# MD029A_HalfBridges.net
KiCad netlist of a schematic drawn in Altium Designer
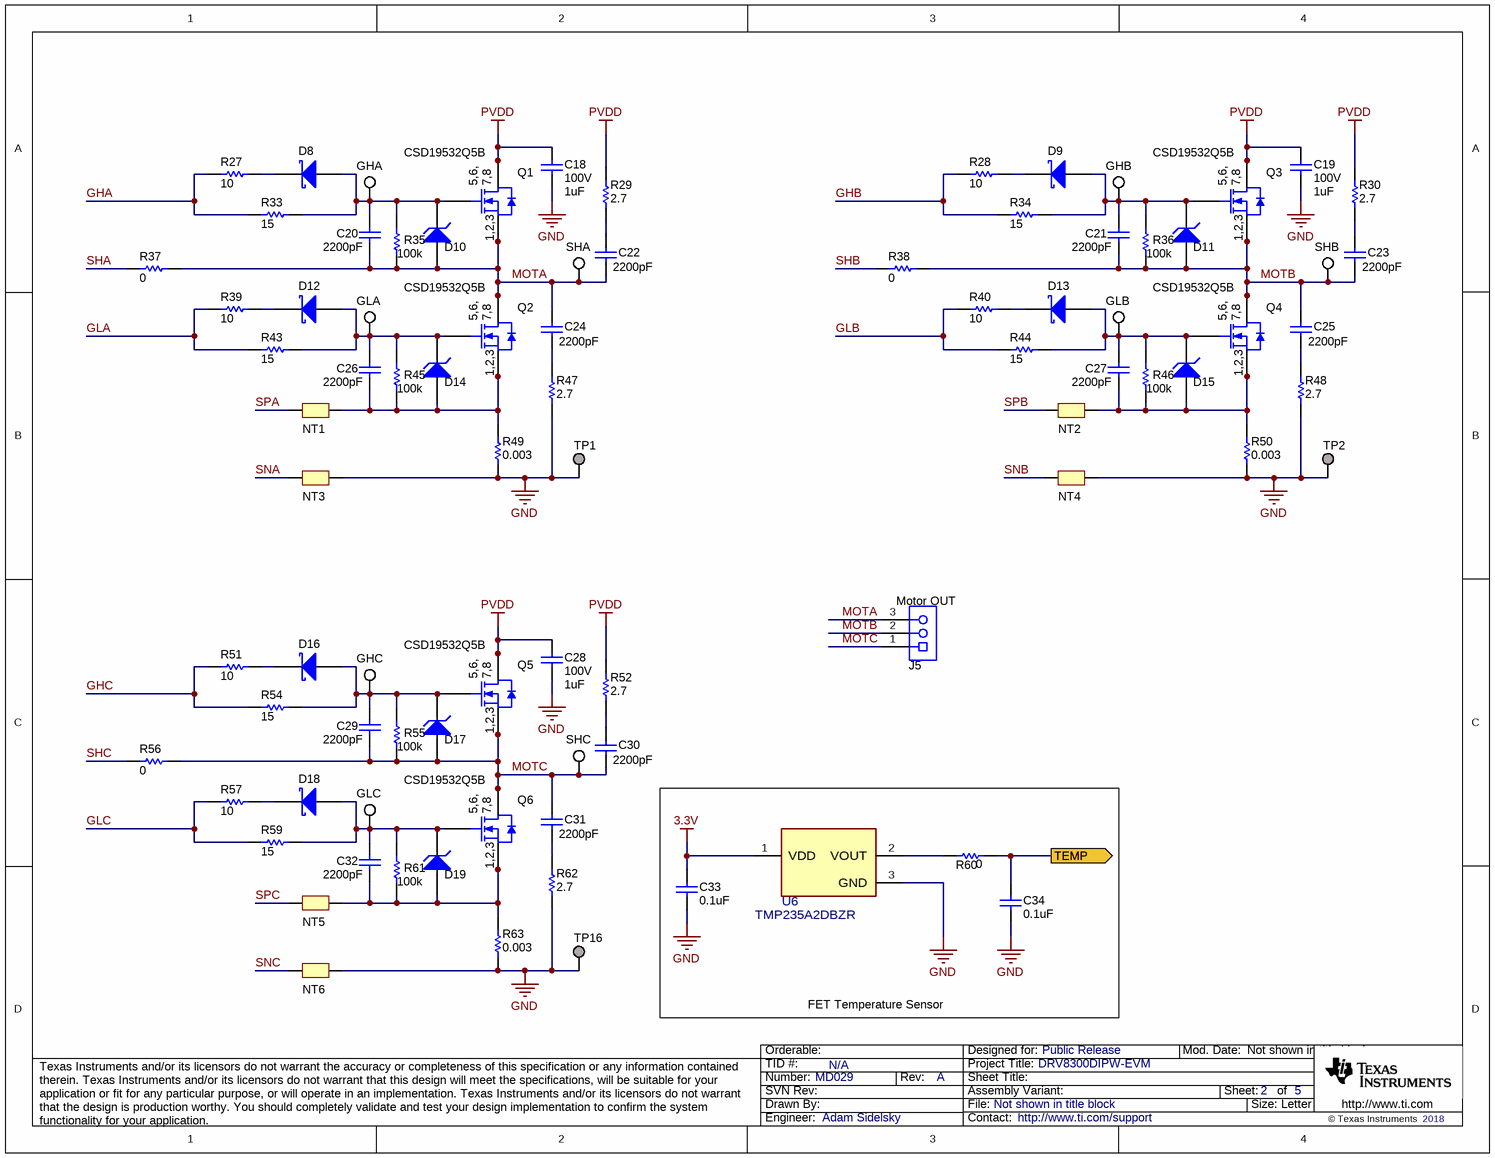
[diagram p0: MD029A_HalfBridges.SchDoc]

(export (version "E")
  (design (tool "Eeschema 10.0.6"))
  (components
    (comp (ref "C18")
      (value "CGA6M2X7R2A105K200AA")
      (footprint "1210_220L")
      (description "CAP, CERM, 1 uF, 100 V, +/- 10%, X7R, AEC-Q200 Grade 1, 1210")
      (fields
        (field (name "MANUFACTURER") "TDK")
        (field (name "VDC_V") "100V")
        (field (name "VALUEDISPLAYED") "1uF")
        (field (name "PUBLISHER") "Texas Instruments")
      )
      (libsource (lib "Altium Vault - TI") (part "Capacitor"))
    )
    (comp (ref "C19")
      (value "CGA6M2X7R2A105K200AA")
      (footprint "1210_220L")
      (description "CAP, CERM, 1 uF, 100 V, +/- 10%, X7R, AEC-Q200 Grade 1, 1210")
      (fields
        (field (name "MANUFACTURER") "TDK")
        (field (name "VDC_V") "100V")
        (field (name "VALUEDISPLAYED") "1uF")
        (field (name "PUBLISHER") "Texas Instruments")
      )
      (libsource (lib "Altium Vault - TI") (part "Capacitor"))
    )
    (comp (ref "C20")
      (value "06031C222KAT2A")
      (footprint "0603L")
      (description "CAP, CERM, 2200 pF, 100 V, +/- 10%, X7R, 0603")
      (fields
        (field (name "MANUFACTURER") "AVX")
        (field (name "VALUEDISPLAYED") "2200pF")
        (field (name "PUBLISHER") "Texas Instruments")
      )
      (libsource (lib "Altium Vault - TI") (part "CMP-0006737-4"))
    )
    (comp (ref "C21")
      (value "06031C222KAT2A")
      (footprint "0603L")
      (description "CAP, CERM, 2200 pF, 100 V, +/- 10%, X7R, 0603")
      (fields
        (field (name "MANUFACTURER") "AVX")
        (field (name "VALUEDISPLAYED") "2200pF")
        (field (name "PUBLISHER") "Texas Instruments")
      )
      (libsource (lib "Altium Vault - TI") (part "CMP-0006737-4"))
    )
    (comp (ref "C22")
      (value "GRM188R72A222KA01D")
      (footprint "0603L")
      (description "CAP, CERM, 2200 pF, 100 V, +/- 10%, X7R, 0603")
      (fields
        (field (name "MANUFACTURER") "MuRata")
        (field (name "VALUEDISPLAYED") "2200pF")
        (field (name "PUBLISHER") "Texas Instruments")
      )
      (libsource (lib "Altium Vault - TI") (part "CMP-0007475-4"))
    )
    (comp (ref "C23")
      (value "GRM188R72A222KA01D")
      (footprint "0603L")
      (description "CAP, CERM, 2200 pF, 100 V, +/- 10%, X7R, 0603")
      (fields
        (field (name "MANUFACTURER") "MuRata")
        (field (name "VALUEDISPLAYED") "2200pF")
        (field (name "PUBLISHER") "Texas Instruments")
      )
      (libsource (lib "Altium Vault - TI") (part "CMP-0007475-4"))
    )
    (comp (ref "C24")
      (value "GRM188R72A222KA01D")
      (footprint "0603L")
      (description "CAP, CERM, 2200 pF, 100 V, +/- 10%, X7R, 0603")
      (fields
        (field (name "MANUFACTURER") "MuRata")
        (field (name "VALUEDISPLAYED") "2200pF")
        (field (name "PUBLISHER") "Texas Instruments")
      )
      (libsource (lib "Altium Vault - TI") (part "CMP-0007475-4"))
    )
    (comp (ref "C25")
      (value "GRM188R72A222KA01D")
      (footprint "0603L")
      (description "CAP, CERM, 2200 pF, 100 V, +/- 10%, X7R, 0603")
      (fields
        (field (name "MANUFACTURER") "MuRata")
        (field (name "VALUEDISPLAYED") "2200pF")
        (field (name "PUBLISHER") "Texas Instruments")
      )
      (libsource (lib "Altium Vault - TI") (part "CMP-0007475-4"))
    )
    (comp (ref "C26")
      (value "06031C222KAT2A")
      (footprint "0603L")
      (description "CAP, CERM, 2200 pF, 100 V, +/- 10%, X7R, 0603")
      (fields
        (field (name "MANUFACTURER") "AVX")
        (field (name "VALUEDISPLAYED") "2200pF")
        (field (name "PUBLISHER") "Texas Instruments")
      )
      (libsource (lib "Altium Vault - TI") (part "CMP-0006737-4"))
    )
    (comp (ref "C27")
      (value "06031C222KAT2A")
      (footprint "0603L")
      (description "CAP, CERM, 2200 pF, 100 V, +/- 10%, X7R, 0603")
      (fields
        (field (name "MANUFACTURER") "AVX")
        (field (name "VALUEDISPLAYED") "2200pF")
        (field (name "PUBLISHER") "Texas Instruments")
      )
      (libsource (lib "Altium Vault - TI") (part "CMP-0006737-4"))
    )
    (comp (ref "C28")
      (value "CGA6M2X7R2A105K200AA")
      (footprint "1210_220L")
      (description "CAP, CERM, 1 uF, 100 V, +/- 10%, X7R, AEC-Q200 Grade 1, 1210")
      (fields
        (field (name "MANUFACTURER") "TDK")
        (field (name "VDC_V") "100V")
        (field (name "VALUEDISPLAYED") "1uF")
        (field (name "PUBLISHER") "Texas Instruments")
      )
      (libsource (lib "Altium Vault - TI") (part "Capacitor"))
    )
    (comp (ref "C29")
      (value "06031C222KAT2A")
      (footprint "0603L")
      (description "CAP, CERM, 2200 pF, 100 V, +/- 10%, X7R, 0603")
      (fields
        (field (name "MANUFACTURER") "AVX")
        (field (name "VALUEDISPLAYED") "2200pF")
        (field (name "PUBLISHER") "Texas Instruments")
      )
      (libsource (lib "Altium Vault - TI") (part "CMP-0006737-4"))
    )
    (comp (ref "C30")
      (value "GRM188R72A222KA01D")
      (footprint "0603L")
      (description "CAP, CERM, 2200 pF, 100 V, +/- 10%, X7R, 0603")
      (fields
        (field (name "MANUFACTURER") "MuRata")
        (field (name "VALUEDISPLAYED") "2200pF")
        (field (name "PUBLISHER") "Texas Instruments")
      )
      (libsource (lib "Altium Vault - TI") (part "CMP-0007475-4"))
    )
    (comp (ref "C31")
      (value "GRM188R72A222KA01D")
      (footprint "0603L")
      (description "CAP, CERM, 2200 pF, 100 V, +/- 10%, X7R, 0603")
      (fields
        (field (name "MANUFACTURER") "MuRata")
        (field (name "VALUEDISPLAYED") "2200pF")
        (field (name "PUBLISHER") "Texas Instruments")
      )
      (libsource (lib "Altium Vault - TI") (part "CMP-0007475-4"))
    )
    (comp (ref "C32")
      (value "06031C222KAT2A")
      (footprint "0603L")
      (description "CAP, CERM, 2200 pF, 100 V, +/- 10%, X7R, 0603")
      (fields
        (field (name "MANUFACTURER") "AVX")
        (field (name "VALUEDISPLAYED") "2200pF")
        (field (name "PUBLISHER") "Texas Instruments")
      )
      (libsource (lib "Altium Vault - TI") (part "CMP-0006737-4"))
    )
    (comp (ref "C33")
      (value "C0603C104J4RACTU")
      (footprint "0603L")
      (description "CAP, CERM, 0.1 uF, 16 V, +/- 5%, X7R, 0603")
      (fields
        (field (name "VALUEDISPLAYED") "0.1uF")
        (field (name "MANUFACTURER") "Kemet")
        (field (name "PUBLISHER") "Texas Instruments")
      )
      (libsource (lib "Altium Vault - TI") (part "CMP-0006857-4"))
    )
    (comp (ref "C34")
      (value "C0603C104J4RACTU")
      (footprint "0603L")
      (description "CAP, CERM, 0.1 uF, 16 V, +/- 5%, X7R, 0603")
      (fields
        (field (name "VALUEDISPLAYED") "0.1uF")
        (field (name "MANUFACTURER") "Kemet")
        (field (name "PUBLISHER") "Texas Instruments")
      )
      (libsource (lib "Altium Vault - TI") (part "CMP-0006857-4"))
    )
    (comp (ref "D8")
      (value "SSA24-E3/61T")
      (footprint "SMA")
      (description "Diode, Schottky, 40 V, 2 A, SMA")
      (fields (field (name "MANUFACTURER") "Vishay-Semiconductor"))
      (libsource (lib "Altium Vault - TI") (part "DIODE_SCHOTTKY"))
    )
    (comp (ref "D9")
      (value "SSA24-E3/61T")
      (footprint "SMA")
      (description "Diode, Schottky, 40 V, 2 A, SMA")
      (fields (field (name "MANUFACTURER") "Vishay-Semiconductor"))
      (libsource (lib "Altium Vault - TI") (part "DIODE_SCHOTTKY"))
    )
    (comp (ref "D10")
      (value "SMAZ16-13-F")
      (footprint "SMA")
      (description "Diode, Zener, 16 V, 1 W, SMA")
      (fields (field (name "MANUFACTURER") "Diodes Inc."))
      (libsource (lib "Altium Vault - TI") (part "Zener"))
    )
    (comp (ref "D11")
      (value "SMAZ16-13-F")
      (footprint "SMA")
      (description "Diode, Zener, 16 V, 1 W, SMA")
      (fields (field (name "MANUFACTURER") "Diodes Inc."))
      (libsource (lib "Altium Vault - TI") (part "Zener"))
    )
    (comp (ref "D12")
      (value "SSA24-E3/61T")
      (footprint "SMA")
      (description "Diode, Schottky, 40 V, 2 A, SMA")
      (fields (field (name "MANUFACTURER") "Vishay-Semiconductor"))
      (libsource (lib "Altium Vault - TI") (part "DIODE_SCHOTTKY"))
    )
    (comp (ref "D13")
      (value "SSA24-E3/61T")
      (footprint "SMA")
      (description "Diode, Schottky, 40 V, 2 A, SMA")
      (fields (field (name "MANUFACTURER") "Vishay-Semiconductor"))
      (libsource (lib "Altium Vault - TI") (part "DIODE_SCHOTTKY"))
    )
    (comp (ref "D14")
      (value "SMAZ16-13-F")
      (footprint "SMA")
      (description "Diode, Zener, 16 V, 1 W, SMA")
      (fields (field (name "MANUFACTURER") "Diodes Inc."))
      (libsource (lib "Altium Vault - TI") (part "Zener"))
    )
    (comp (ref "D15")
      (value "SMAZ16-13-F")
      (footprint "SMA")
      (description "Diode, Zener, 16 V, 1 W, SMA")
      (fields (field (name "MANUFACTURER") "Diodes Inc."))
      (libsource (lib "Altium Vault - TI") (part "Zener"))
    )
    (comp (ref "D16")
      (value "SSA24-E3/61T")
      (footprint "SMA")
      (description "Diode, Schottky, 40 V, 2 A, SMA")
      (fields (field (name "MANUFACTURER") "Vishay-Semiconductor"))
      (libsource (lib "Altium Vault - TI") (part "DIODE_SCHOTTKY"))
    )
    (comp (ref "D17")
      (value "SMAZ16-13-F")
      (footprint "SMA")
      (description "Diode, Zener, 16 V, 1 W, SMA")
      (fields (field (name "MANUFACTURER") "Diodes Inc."))
      (libsource (lib "Altium Vault - TI") (part "Zener"))
    )
    (comp (ref "D18")
      (value "SSA24-E3/61T")
      (footprint "SMA")
      (description "Diode, Schottky, 40 V, 2 A, SMA")
      (fields (field (name "MANUFACTURER") "Vishay-Semiconductor"))
      (libsource (lib "Altium Vault - TI") (part "DIODE_SCHOTTKY"))
    )
    (comp (ref "D19")
      (value "SMAZ16-13-F")
      (footprint "SMA")
      (description "Diode, Zener, 16 V, 1 W, SMA")
      (fields (field (name "MANUFACTURER") "Diodes Inc."))
      (libsource (lib "Altium Vault - TI") (part "Zener"))
    )
    (comp (ref "GHA")
      (value "5002")
      (footprint "Keystone5002")
      (description "Test Point, Miniature, White, TH")
      (fields (field (name "MANUFACTURER") "Keystone") (field (name "PUBLISHER") "Texas Instruments"))
      (libsource (lib "Altium Vault - TI") (part "5002"))
    )
    (comp (ref "GHB")
      (value "5002")
      (footprint "Keystone5002")
      (description "Test Point, Miniature, White, TH")
      (fields (field (name "MANUFACTURER") "Keystone") (field (name "PUBLISHER") "Texas Instruments"))
      (libsource (lib "Altium Vault - TI") (part "5002"))
    )
    (comp (ref "GHC")
      (value "5002")
      (footprint "Keystone5002")
      (description "Test Point, Miniature, White, TH")
      (fields (field (name "MANUFACTURER") "Keystone") (field (name "PUBLISHER") "Texas Instruments"))
      (libsource (lib "Altium Vault - TI") (part "5002"))
    )
    (comp (ref "GLA")
      (value "5002")
      (footprint "Keystone5002")
      (description "Test Point, Miniature, White, TH")
      (fields (field (name "MANUFACTURER") "Keystone") (field (name "PUBLISHER") "Texas Instruments"))
      (libsource (lib "Altium Vault - TI") (part "5002"))
    )
    (comp (ref "GLB")
      (value "5002")
      (footprint "Keystone5002")
      (description "Test Point, Miniature, White, TH")
      (fields (field (name "MANUFACTURER") "Keystone") (field (name "PUBLISHER") "Texas Instruments"))
      (libsource (lib "Altium Vault - TI") (part "5002"))
    )
    (comp (ref "GLC")
      (value "5002")
      (footprint "Keystone5002")
      (description "Test Point, Miniature, White, TH")
      (fields (field (name "MANUFACTURER") "Keystone") (field (name "PUBLISHER") "Texas Instruments"))
      (libsource (lib "Altium Vault - TI") (part "5002"))
    )
    (comp (ref "J5")
      (value "Motor OUT")
      (footprint "Phoenix_1904150")
      (description "Terminal Block, 9.52mm, 3x1, R/A, TH")
      (fields
        (field (name "PARTNUMBER") "1904150")
        (field (name "MANUFACTURER") "Phoenix Contact")
        (field (name "PUBLISHER") "Texas Instruments")
      )
      (libsource (lib "Altium Vault - TI") (part "CMP-0055528-1"))
    )
    (comp (ref "NT1")
      (value "Net-Tie")
      (footprint "Net-Tie_10mil")
      (description "Single point connection between nets.")
      (libsource (lib "Altium Vault - TI") (part "Net-Tie"))
    )
    (comp (ref "NT2")
      (value "Net-Tie")
      (footprint "Net-Tie_10mil")
      (description "Single point connection between nets.")
      (libsource (lib "Altium Vault - TI") (part "Net-Tie"))
    )
    (comp (ref "NT3")
      (value "Net-Tie")
      (footprint "Net-Tie_10mil")
      (description "Single point connection between nets.")
      (libsource (lib "Altium Vault - TI") (part "Net-Tie"))
    )
    (comp (ref "NT4")
      (value "Net-Tie")
      (footprint "Net-Tie_10mil")
      (description "Single point connection between nets.")
      (libsource (lib "Altium Vault - TI") (part "Net-Tie"))
    )
    (comp (ref "NT5")
      (value "Net-Tie")
      (footprint "Net-Tie_10mil")
      (description "Single point connection between nets.")
      (libsource (lib "Altium Vault - TI") (part "Net-Tie"))
    )
    (comp (ref "NT6")
      (value "Net-Tie")
      (footprint "Net-Tie_10mil")
      (description "Single point connection between nets.")
      (libsource (lib "Altium Vault - TI") (part "Net-Tie"))
    )
    (comp (ref "Q1")
      (value "CSD19532Q5B")
      (footprint "DNK0008A")
      (description "MOSFET, N-CH, 100 V, 17 A, DNK0008A (VSON-CLIP-8)")
      (fields (field (name "MANUFACTURER") "Texas Instruments"))
      (libsource (lib "Altium Vault - TI") (part "MOSFET_N_D56789G4S123"))
    )
    (comp (ref "Q2")
      (value "CSD19532Q5B")
      (footprint "DNK0008A")
      (description "MOSFET, N-CH, 100 V, 17 A, DNK0008A (VSON-CLIP-8)")
      (fields (field (name "MANUFACTURER") "Texas Instruments"))
      (libsource (lib "Altium Vault - TI") (part "MOSFET_N_D56789G4S123"))
    )
    (comp (ref "Q3")
      (value "CSD19532Q5B")
      (footprint "DNK0008A")
      (description "MOSFET, N-CH, 100 V, 17 A, DNK0008A (VSON-CLIP-8)")
      (fields (field (name "MANUFACTURER") "Texas Instruments"))
      (libsource (lib "Altium Vault - TI") (part "MOSFET_N_D56789G4S123"))
    )
    (comp (ref "Q4")
      (value "CSD19532Q5B")
      (footprint "DNK0008A")
      (description "MOSFET, N-CH, 100 V, 17 A, DNK0008A (VSON-CLIP-8)")
      (fields (field (name "MANUFACTURER") "Texas Instruments"))
      (libsource (lib "Altium Vault - TI") (part "MOSFET_N_D56789G4S123"))
    )
    (comp (ref "Q5")
      (value "CSD19532Q5B")
      (footprint "DNK0008A")
      (description "MOSFET, N-CH, 100 V, 17 A, DNK0008A (VSON-CLIP-8)")
      (fields (field (name "MANUFACTURER") "Texas Instruments"))
      (libsource (lib "Altium Vault - TI") (part "MOSFET_N_D56789G4S123"))
    )
    (comp (ref "Q6")
      (value "CSD19532Q5B")
      (footprint "DNK0008A")
      (description "MOSFET, N-CH, 100 V, 17 A, DNK0008A (VSON-CLIP-8)")
      (fields (field (name "MANUFACTURER") "Texas Instruments"))
      (libsource (lib "Altium Vault - TI") (part "MOSFET_N_D56789G4S123"))
    )
    (comp (ref "R27")
      (value "ERJ-6GEYJ100V")
      (footprint "0805L")
      (description "RES, 10, 5%, 0.125 W, AEC-Q200 Grade 0, 0805")
      (fields (field (name "MANUFACTURER") "Panasonic") (field (name "VALUEDISPLAYED") "10"))
      (libsource (lib "Altium Vault - TI") (part "Resistor"))
    )
    (comp (ref "R28")
      (value "ERJ-6GEYJ100V")
      (footprint "0805L")
      (description "RES, 10, 5%, 0.125 W, AEC-Q200 Grade 0, 0805")
      (fields (field (name "MANUFACTURER") "Panasonic") (field (name "VALUEDISPLAYED") "10"))
      (libsource (lib "Altium Vault - TI") (part "Resistor"))
    )
    (comp (ref "R29")
      (value "CRCW08052R70JNEA")
      (footprint "0805L")
      (description "RES, 2.7, 5%, 0.125 W, AEC-Q200 Grade 0, 0805")
      (fields (field (name "MANUFACTURER") "Vishay-Dale") (field (name "VALUEDISPLAYED") "2.7"))
      (libsource (lib "Altium Vault - TI") (part "Resistor"))
    )
    (comp (ref "R30")
      (value "CRCW08052R70JNEA")
      (footprint "0805L")
      (description "RES, 2.7, 5%, 0.125 W, AEC-Q200 Grade 0, 0805")
      (fields (field (name "MANUFACTURER") "Vishay-Dale") (field (name "VALUEDISPLAYED") "2.7"))
      (libsource (lib "Altium Vault - TI") (part "Resistor"))
    )
    (comp (ref "R33")
      (value "ERJ-6GEYJ150V")
      (footprint "0805L")
      (description "RES, 15, 5%, 0.125 W, AEC-Q200 Grade 0, 0805")
      (fields (field (name "MANUFACTURER") "Panasonic") (field (name "VALUEDISPLAYED") "15"))
      (libsource (lib "Altium Vault - TI") (part "Resistor"))
    )
    (comp (ref "R34")
      (value "ERJ-6GEYJ150V")
      (footprint "0805L")
      (description "RES, 15, 5%, 0.125 W, AEC-Q200 Grade 0, 0805")
      (fields (field (name "MANUFACTURER") "Panasonic") (field (name "VALUEDISPLAYED") "15"))
      (libsource (lib "Altium Vault - TI") (part "Resistor"))
    )
    (comp (ref "R35")
      (value "CRCW0603100KFKEA")
      (footprint "0603L")
      (description "RES, 100 k, 1%, 0.1 W, AEC-Q200 Grade 0, 0603")
      (fields (field (name "MANUFACTURER") "Vishay-Dale") (field (name "VALUEDISPLAYED") "100k"))
      (libsource (lib "Altium Vault - TI") (part "Resistor"))
    )
    (comp (ref "R36")
      (value "CRCW0603100KFKEA")
      (footprint "0603L")
      (description "RES, 100 k, 1%, 0.1 W, AEC-Q200 Grade 0, 0603")
      (fields (field (name "MANUFACTURER") "Vishay-Dale") (field (name "VALUEDISPLAYED") "100k"))
      (libsource (lib "Altium Vault - TI") (part "Resistor"))
    )
    (comp (ref "R37")
      (value "RCS06030000Z0EA")
      (footprint "0603L")
      (description "RES, 0, 0%, 0.25 W, AEC-Q200 Grade 0, 0603")
      (fields (field (name "MANUFACTURER") "Vishay-Dale") (field (name "VALUEDISPLAYED") "0"))
      (libsource (lib "Altium Vault - TI") (part "Resistor"))
    )
    (comp (ref "R38")
      (value "RCS06030000Z0EA")
      (footprint "0603L")
      (description "RES, 0, 0%, 0.25 W, AEC-Q200 Grade 0, 0603")
      (fields (field (name "MANUFACTURER") "Vishay-Dale") (field (name "VALUEDISPLAYED") "0"))
      (libsource (lib "Altium Vault - TI") (part "Resistor"))
    )
    (comp (ref "R39")
      (value "ERJ-6GEYJ100V")
      (footprint "0805L")
      (description "RES, 10, 5%, 0.125 W, AEC-Q200 Grade 0, 0805")
      (fields (field (name "MANUFACTURER") "Panasonic") (field (name "VALUEDISPLAYED") "10"))
      (libsource (lib "Altium Vault - TI") (part "Resistor"))
    )
    (comp (ref "R40")
      (value "ERJ-6GEYJ100V")
      (footprint "0805L")
      (description "RES, 10, 5%, 0.125 W, AEC-Q200 Grade 0, 0805")
      (fields (field (name "MANUFACTURER") "Panasonic") (field (name "VALUEDISPLAYED") "10"))
      (libsource (lib "Altium Vault - TI") (part "Resistor"))
    )
    (comp (ref "R43")
      (value "ERJ-6GEYJ150V")
      (footprint "0805L")
      (description "RES, 15, 5%, 0.125 W, AEC-Q200 Grade 0, 0805")
      (fields (field (name "MANUFACTURER") "Panasonic") (field (name "VALUEDISPLAYED") "15"))
      (libsource (lib "Altium Vault - TI") (part "Resistor"))
    )
    (comp (ref "R44")
      (value "ERJ-6GEYJ150V")
      (footprint "0805L")
      (description "RES, 15, 5%, 0.125 W, AEC-Q200 Grade 0, 0805")
      (fields (field (name "MANUFACTURER") "Panasonic") (field (name "VALUEDISPLAYED") "15"))
      (libsource (lib "Altium Vault - TI") (part "Resistor"))
    )
    (comp (ref "R45")
      (value "CRCW0603100KFKEA")
      (footprint "0603L")
      (description "RES, 100 k, 1%, 0.1 W, AEC-Q200 Grade 0, 0603")
      (fields (field (name "MANUFACTURER") "Vishay-Dale") (field (name "VALUEDISPLAYED") "100k"))
      (libsource (lib "Altium Vault - TI") (part "Resistor"))
    )
    (comp (ref "R46")
      (value "CRCW0603100KFKEA")
      (footprint "0603L")
      (description "RES, 100 k, 1%, 0.1 W, AEC-Q200 Grade 0, 0603")
      (fields (field (name "MANUFACTURER") "Vishay-Dale") (field (name "VALUEDISPLAYED") "100k"))
      (libsource (lib "Altium Vault - TI") (part "Resistor"))
    )
    (comp (ref "R47")
      (value "CRCW08052R70JNEA")
      (footprint "0805L")
      (description "RES, 2.7, 5%, 0.125 W, AEC-Q200 Grade 0, 0805")
      (fields (field (name "MANUFACTURER") "Vishay-Dale") (field (name "VALUEDISPLAYED") "2.7"))
      (libsource (lib "Altium Vault - TI") (part "Resistor"))
    )
    (comp (ref "R48")
      (value "CRCW08052R70JNEA")
      (footprint "0805L")
      (description "RES, 2.7, 5%, 0.125 W, AEC-Q200 Grade 0, 0805")
      (fields (field (name "MANUFACTURER") "Vishay-Dale") (field (name "VALUEDISPLAYED") "2.7"))
      (libsource (lib "Altium Vault - TI") (part "Resistor"))
    )
    (comp (ref "R49")
      (value "CRE2512-FZ-R003E-3")
      (footprint "CRE2512-R1_R4")
      (description "RES, 0.003, 1%, 3 W, AEC-Q200 Grade 0, 2512")
      (fields
        (field (name "MANUFACTURER") "Bourns")
        (field (name "VALUEDISPLAYED") "0.003")
        (field (name "PUBLISHER") "Texas Instruments")
      )
      (libsource (lib "Altium Vault - TI") (part "Resistor"))
    )
    (comp (ref "R50")
      (value "CRE2512-FZ-R003E-3")
      (footprint "CRE2512-R1_R4")
      (description "RES, 0.003, 1%, 3 W, AEC-Q200 Grade 0, 2512")
      (fields
        (field (name "MANUFACTURER") "Bourns")
        (field (name "VALUEDISPLAYED") "0.003")
        (field (name "PUBLISHER") "Texas Instruments")
      )
      (libsource (lib "Altium Vault - TI") (part "Resistor"))
    )
    (comp (ref "R51")
      (value "ERJ-6GEYJ100V")
      (footprint "0805L")
      (description "RES, 10, 5%, 0.125 W, AEC-Q200 Grade 0, 0805")
      (fields (field (name "MANUFACTURER") "Panasonic") (field (name "VALUEDISPLAYED") "10"))
      (libsource (lib "Altium Vault - TI") (part "Resistor"))
    )
    (comp (ref "R52")
      (value "CRCW08052R70JNEA")
      (footprint "0805L")
      (description "RES, 2.7, 5%, 0.125 W, AEC-Q200 Grade 0, 0805")
      (fields (field (name "MANUFACTURER") "Vishay-Dale") (field (name "VALUEDISPLAYED") "2.7"))
      (libsource (lib "Altium Vault - TI") (part "Resistor"))
    )
    (comp (ref "R54")
      (value "ERJ-6GEYJ150V")
      (footprint "0805L")
      (description "RES, 15, 5%, 0.125 W, AEC-Q200 Grade 0, 0805")
      (fields (field (name "MANUFACTURER") "Panasonic") (field (name "VALUEDISPLAYED") "15"))
      (libsource (lib "Altium Vault - TI") (part "Resistor"))
    )
    (comp (ref "R55")
      (value "CRCW0603100KFKEA")
      (footprint "0603L")
      (description "RES, 100 k, 1%, 0.1 W, AEC-Q200 Grade 0, 0603")
      (fields (field (name "MANUFACTURER") "Vishay-Dale") (field (name "VALUEDISPLAYED") "100k"))
      (libsource (lib "Altium Vault - TI") (part "Resistor"))
    )
    (comp (ref "R56")
      (value "RCS06030000Z0EA")
      (footprint "0603L")
      (description "RES, 0, 0%, 0.25 W, AEC-Q200 Grade 0, 0603")
      (fields (field (name "MANUFACTURER") "Vishay-Dale") (field (name "VALUEDISPLAYED") "0"))
      (libsource (lib "Altium Vault - TI") (part "Resistor"))
    )
    (comp (ref "R57")
      (value "ERJ-6GEYJ100V")
      (footprint "0805L")
      (description "RES, 10, 5%, 0.125 W, AEC-Q200 Grade 0, 0805")
      (fields (field (name "MANUFACTURER") "Panasonic") (field (name "VALUEDISPLAYED") "10"))
      (libsource (lib "Altium Vault - TI") (part "Resistor"))
    )
    (comp (ref "R59")
      (value "ERJ-6GEYJ150V")
      (footprint "0805L")
      (description "RES, 15, 5%, 0.125 W, AEC-Q200 Grade 0, 0805")
      (fields (field (name "MANUFACTURER") "Panasonic") (field (name "VALUEDISPLAYED") "15"))
      (libsource (lib "Altium Vault - TI") (part "Resistor"))
    )
    (comp (ref "R60")
      (value "0")
      (footprint "0603L")
      (description "RES, 0, 5%, 0.1 W, AEC-Q200 Grade 0, 0603")
      (fields (field (name "PARTNUMBER") "CRCW06030000Z0EA") (field (name "MANUFACTURER") "Vishay-Dale"))
      (libsource (lib "Altium Vault - TI") (part "Resistor"))
    )
    (comp (ref "R61")
      (value "CRCW0603100KFKEA")
      (footprint "0603L")
      (description "RES, 100 k, 1%, 0.1 W, AEC-Q200 Grade 0, 0603")
      (fields (field (name "MANUFACTURER") "Vishay-Dale") (field (name "VALUEDISPLAYED") "100k"))
      (libsource (lib "Altium Vault - TI") (part "Resistor"))
    )
    (comp (ref "R62")
      (value "CRCW08052R70JNEA")
      (footprint "0805L")
      (description "RES, 2.7, 5%, 0.125 W, AEC-Q200 Grade 0, 0805")
      (fields (field (name "MANUFACTURER") "Vishay-Dale") (field (name "VALUEDISPLAYED") "2.7"))
      (libsource (lib "Altium Vault - TI") (part "Resistor"))
    )
    (comp (ref "R63")
      (value "CRE2512-FZ-R003E-3")
      (footprint "CRE2512-R1_R4")
      (description "RES, 0.003, 1%, 3 W, AEC-Q200 Grade 0, 2512")
      (fields
        (field (name "MANUFACTURER") "Bourns")
        (field (name "VALUEDISPLAYED") "0.003")
        (field (name "PUBLISHER") "Texas Instruments")
      )
      (libsource (lib "Altium Vault - TI") (part "Resistor"))
    )
    (comp (ref "SHA")
      (value "5002")
      (footprint "Keystone5002")
      (description "Test Point, Miniature, White, TH")
      (fields (field (name "MANUFACTURER") "Keystone") (field (name "PUBLISHER") "Texas Instruments"))
      (libsource (lib "Altium Vault - TI") (part "5002"))
    )
    (comp (ref "SHB")
      (value "5002")
      (footprint "Keystone5002")
      (description "Test Point, Miniature, White, TH")
      (fields (field (name "MANUFACTURER") "Keystone") (field (name "PUBLISHER") "Texas Instruments"))
      (libsource (lib "Altium Vault - TI") (part "5002"))
    )
    (comp (ref "SHC")
      (value "5002")
      (footprint "Keystone5002")
      (description "Test Point, Miniature, White, TH")
      (fields (field (name "MANUFACTURER") "Keystone") (field (name "PUBLISHER") "Texas Instruments"))
      (libsource (lib "Altium Vault - TI") (part "5002"))
    )
    (comp (ref "TP1")
      (value "TP_SM_1MM")
      (footprint "TP_SM_1MM")
      (description "1mm Test Point, SMT")
      (fields (field (name "MANUFACTURER") "Any") (field (name "PUBLISHER") "Texas Instruments"))
      (libsource (lib "Altium Vault - TI") (part "TESTPOINT"))
    )
    (comp (ref "TP2")
      (value "TP_SM_1MM")
      (footprint "TP_SM_1MM")
      (description "1mm Test Point, SMT")
      (fields (field (name "MANUFACTURER") "Any") (field (name "PUBLISHER") "Texas Instruments"))
      (libsource (lib "Altium Vault - TI") (part "TESTPOINT"))
    )
    (comp (ref "TP16")
      (value "TP_SM_1MM")
      (footprint "TP_SM_1MM")
      (description "1mm Test Point, SMT")
      (fields (field (name "MANUFACTURER") "Any") (field (name "PUBLISHER") "Texas Instruments"))
      (libsource (lib "Altium Vault - TI") (part "TESTPOINT"))
    )
    (comp (ref "U6")
      (value "TMP235A2DBZR")
      (footprint "DBZ0003A-MFG")
      (description "Temperature Sensor Analog, Local -40°C ~ 150°C 10mV/°C SOT-23-3")
      (fields
        (field (name "DIGIKEY PART NUMBER") "296-TMP235A2DBZRCT-ND")
        (field (name "MANUFACTURER") "Texas Instruments")
      )
      (libsource (lib "Altium Vault - TI") (part "SYM-TMP235A2DBZR"))
    )
  )
  (nets
    (net (code "1") (name "/GHA") (class "Default")
      (node (ref "R27") (pin "1") (pinfunction "1_1") (pintype "passive"))
      (node (ref "R33") (pin "1") (pinfunction "1_1") (pintype "passive"))
    )
    (net (code "2") (name "/GHB") (class "Default")
      (node (ref "R28") (pin "1") (pinfunction "1_1") (pintype "passive"))
      (node (ref "R34") (pin "1") (pinfunction "1_1") (pintype "passive"))
    )
    (net (code "3") (name "/GHC") (class "Default")
      (node (ref "R51") (pin "1") (pinfunction "1_1") (pintype "passive"))
      (node (ref "R54") (pin "1") (pinfunction "1_1") (pintype "passive"))
    )
    (net (code "4") (name "/GLA") (class "Default")
      (node (ref "R39") (pin "1") (pinfunction "1_1") (pintype "passive"))
      (node (ref "R43") (pin "1") (pinfunction "1_1") (pintype "passive"))
    )
    (net (code "5") (name "/GLB") (class "Default")
      (node (ref "R40") (pin "1") (pinfunction "1_1") (pintype "passive"))
      (node (ref "R44") (pin "1") (pinfunction "1_1") (pintype "passive"))
    )
    (net (code "6") (name "/GLC") (class "Default")
      (node (ref "R57") (pin "1") (pinfunction "1_1") (pintype "passive"))
      (node (ref "R59") (pin "1") (pinfunction "1_1") (pintype "passive"))
    )
    (net (code "7") (name "/MOTA") (class "Default")
      (node (ref "C20") (pin "2") (pinfunction "2_2") (pintype "passive"))
      (node (ref "C22") (pin "2") (pinfunction "2_2") (pintype "passive"))
      (node (ref "C24") (pin "1") (pinfunction "1_1") (pintype "passive"))
      (node (ref "D10") (pin "2") (pinfunction "A_2") (pintype "passive"))
      (node (ref "J5") (pin "3") (pinfunction "3_3") (pintype "passive"))
      (node (ref "Q1") (pin "1") (pinfunction "S_1") (pintype "passive"))
      (node (ref "Q1") (pin "2") (pinfunction "S_2") (pintype "passive"))
      (node (ref "Q1") (pin "3") (pinfunction "S_3") (pintype "passive"))
      (node (ref "Q2") (pin "5") (pinfunction "D_5") (pintype "passive"))
      (node (ref "Q2") (pin "6") (pinfunction "D_6") (pintype "passive"))
      (node (ref "Q2") (pin "7") (pinfunction "D_7") (pintype "passive"))
      (node (ref "Q2") (pin "8") (pinfunction "D_8") (pintype "passive"))
      (node (ref "Q2") (pin "9") (pinfunction "D_9") (pintype "passive"))
      (node (ref "R35") (pin "2") (pinfunction "2_2") (pintype "passive"))
      (node (ref "R37") (pin "2") (pinfunction "2_2") (pintype "passive"))
      (node (ref "SHA") (pin "1") (pintype "passive"))
    )
    (net (code "8") (name "/MOTB") (class "Default")
      (node (ref "C21") (pin "2") (pinfunction "2_2") (pintype "passive"))
      (node (ref "C23") (pin "2") (pinfunction "2_2") (pintype "passive"))
      (node (ref "C25") (pin "1") (pinfunction "1_1") (pintype "passive"))
      (node (ref "D11") (pin "2") (pinfunction "A_2") (pintype "passive"))
      (node (ref "J5") (pin "2") (pinfunction "2_2") (pintype "passive"))
      (node (ref "Q3") (pin "1") (pinfunction "S_1") (pintype "passive"))
      (node (ref "Q3") (pin "2") (pinfunction "S_2") (pintype "passive"))
      (node (ref "Q3") (pin "3") (pinfunction "S_3") (pintype "passive"))
      (node (ref "Q4") (pin "5") (pinfunction "D_5") (pintype "passive"))
      (node (ref "Q4") (pin "6") (pinfunction "D_6") (pintype "passive"))
      (node (ref "Q4") (pin "7") (pinfunction "D_7") (pintype "passive"))
      (node (ref "Q4") (pin "8") (pinfunction "D_8") (pintype "passive"))
      (node (ref "Q4") (pin "9") (pinfunction "D_9") (pintype "passive"))
      (node (ref "R36") (pin "2") (pinfunction "2_2") (pintype "passive"))
      (node (ref "R38") (pin "2") (pinfunction "2_2") (pintype "passive"))
      (node (ref "SHB") (pin "1") (pintype "passive"))
    )
    (net (code "9") (name "/MOTC") (class "Default")
      (node (ref "C29") (pin "2") (pinfunction "2_2") (pintype "passive"))
      (node (ref "C30") (pin "2") (pinfunction "2_2") (pintype "passive"))
      (node (ref "C31") (pin "1") (pinfunction "1_1") (pintype "passive"))
      (node (ref "D17") (pin "2") (pinfunction "A_2") (pintype "passive"))
      (node (ref "J5") (pin "1") (pinfunction "1_1") (pintype "passive"))
      (node (ref "Q5") (pin "1") (pinfunction "S_1") (pintype "passive"))
      (node (ref "Q5") (pin "2") (pinfunction "S_2") (pintype "passive"))
      (node (ref "Q5") (pin "3") (pinfunction "S_3") (pintype "passive"))
      (node (ref "Q6") (pin "5") (pinfunction "D_5") (pintype "passive"))
      (node (ref "Q6") (pin "6") (pinfunction "D_6") (pintype "passive"))
      (node (ref "Q6") (pin "7") (pinfunction "D_7") (pintype "passive"))
      (node (ref "Q6") (pin "8") (pinfunction "D_8") (pintype "passive"))
      (node (ref "Q6") (pin "9") (pinfunction "D_9") (pintype "passive"))
      (node (ref "R55") (pin "2") (pinfunction "2_2") (pintype "passive"))
      (node (ref "R56") (pin "2") (pinfunction "2_2") (pintype "passive"))
      (node (ref "SHC") (pin "1") (pintype "passive"))
    )
    (net (code "10") (name "/SHA") (class "Default")
      (node (ref "R37") (pin "1") (pinfunction "1_1") (pintype "passive"))
    )
    (net (code "11") (name "/SHB") (class "Default")
      (node (ref "R38") (pin "1") (pinfunction "1_1") (pintype "passive"))
    )
    (net (code "12") (name "/SHC") (class "Default")
      (node (ref "R56") (pin "1") (pinfunction "1_1") (pintype "passive"))
    )
    (net (code "13") (name "/SNA") (class "Default")
      (node (ref "NT3") (pin "1") (pinfunction "1_1") (pintype "passive"))
    )
    (net (code "14") (name "/SNB") (class "Default")
      (node (ref "NT4") (pin "1") (pinfunction "1_1") (pintype "passive"))
    )
    (net (code "15") (name "/SNC") (class "Default")
      (node (ref "NT6") (pin "1") (pinfunction "1_1") (pintype "passive"))
    )
    (net (code "16") (name "/SPA") (class "Default")
      (node (ref "NT1") (pin "1") (pinfunction "1_1") (pintype "passive"))
    )
    (net (code "17") (name "/SPB") (class "Default")
      (node (ref "NT2") (pin "1") (pinfunction "1_1") (pintype "passive"))
    )
    (net (code "18") (name "/SPC") (class "Default")
      (node (ref "NT5") (pin "1") (pinfunction "1_1") (pintype "passive"))
    )
    (net (code "19") (name "/TEMP") (class "Default")
      (node (ref "C34") (pin "1") (pinfunction "1_1") (pintype "passive"))
      (node (ref "R60") (pin "1") (pinfunction "1_1") (pintype "passive"))
    )
    (net (code "20") (name "3.3V") (class "Default")
      (node (ref "C33") (pin "1") (pinfunction "1_1") (pintype "passive"))
      (node (ref "U6") (pin "1") (pinfunction "VDD_1") (pintype "power_in"))
    )
    (net (code "21") (name "GND") (class "Default")
      (node (ref "C18") (pin "2") (pinfunction "2_2") (pintype "passive"))
      (node (ref "C19") (pin "2") (pinfunction "2_2") (pintype "passive"))
      (node (ref "C28") (pin "2") (pinfunction "2_2") (pintype "passive"))
      (node (ref "C33") (pin "2") (pinfunction "2_2") (pintype "passive"))
      (node (ref "C34") (pin "2") (pinfunction "2_2") (pintype "passive"))
      (node (ref "NT3") (pin "2") (pinfunction "2_2") (pintype "passive"))
      (node (ref "NT4") (pin "2") (pinfunction "2_2") (pintype "passive"))
      (node (ref "NT6") (pin "2") (pinfunction "2_2") (pintype "passive"))
      (node (ref "R47") (pin "1") (pinfunction "1_1") (pintype "passive"))
      (node (ref "R48") (pin "1") (pinfunction "1_1") (pintype "passive"))
      (node (ref "R49") (pin "1") (pinfunction "1_1") (pintype "passive"))
      (node (ref "R50") (pin "1") (pinfunction "1_1") (pintype "passive"))
      (node (ref "R62") (pin "1") (pinfunction "1_1") (pintype "passive"))
      (node (ref "R63") (pin "1") (pinfunction "1_1") (pintype "passive"))
      (node (ref "TP1") (pin "1") (pintype "passive"))
      (node (ref "TP16") (pin "1") (pintype "passive"))
      (node (ref "TP2") (pin "1") (pintype "passive"))
      (node (ref "U6") (pin "3") (pinfunction "GND_3") (pintype "power_in"))
    )
    (net (code "22") (name "Net-(C22-Pad1)") (class "Default")
      (node (ref "C22") (pin "1") (pinfunction "1_1") (pintype "passive"))
      (node (ref "R29") (pin "1") (pinfunction "1_1") (pintype "passive"))
    )
    (net (code "23") (name "Net-(C23-Pad1)") (class "Default")
      (node (ref "C23") (pin "1") (pinfunction "1_1") (pintype "passive"))
      (node (ref "R30") (pin "1") (pinfunction "1_1") (pintype "passive"))
    )
    (net (code "24") (name "Net-(C24-Pad2)") (class "Default")
      (node (ref "C24") (pin "2") (pinfunction "2_2") (pintype "passive"))
      (node (ref "R47") (pin "2") (pinfunction "2_2") (pintype "passive"))
    )
    (net (code "25") (name "Net-(C25-Pad2)") (class "Default")
      (node (ref "C25") (pin "2") (pinfunction "2_2") (pintype "passive"))
      (node (ref "R48") (pin "2") (pinfunction "2_2") (pintype "passive"))
    )
    (net (code "26") (name "Net-(C30-Pad1)") (class "Default")
      (node (ref "C30") (pin "1") (pinfunction "1_1") (pintype "passive"))
      (node (ref "R52") (pin "1") (pinfunction "1_1") (pintype "passive"))
    )
    (net (code "27") (name "Net-(C31-Pad2)") (class "Default")
      (node (ref "C31") (pin "2") (pinfunction "2_2") (pintype "passive"))
      (node (ref "R62") (pin "2") (pinfunction "2_2") (pintype "passive"))
    )
    (net (code "28") (name "Net-(D8-K)") (class "Default")
      (node (ref "D8") (pin "1") (pinfunction "K_1") (pintype "passive"))
      (node (ref "R27") (pin "2") (pinfunction "2_2") (pintype "passive"))
    )
    (net (code "29") (name "Net-(D9-K)") (class "Default")
      (node (ref "D9") (pin "1") (pinfunction "K_1") (pintype "passive"))
      (node (ref "R28") (pin "2") (pinfunction "2_2") (pintype "passive"))
    )
    (net (code "30") (name "Net-(D10-K)") (class "Default")
      (node (ref "C20") (pin "1") (pinfunction "1_1") (pintype "passive"))
      (node (ref "D10") (pin "1") (pinfunction "K_1") (pintype "passive"))
      (node (ref "D8") (pin "2") (pinfunction "A_2") (pintype "passive"))
      (node (ref "GHA") (pin "1") (pintype "passive"))
      (node (ref "Q1") (pin "4") (pinfunction "G_4") (pintype "passive"))
      (node (ref "R33") (pin "2") (pinfunction "2_2") (pintype "passive"))
      (node (ref "R35") (pin "1") (pinfunction "1_1") (pintype "passive"))
    )
    (net (code "31") (name "Net-(D11-K)") (class "Default")
      (node (ref "C21") (pin "1") (pinfunction "1_1") (pintype "passive"))
      (node (ref "D11") (pin "1") (pinfunction "K_1") (pintype "passive"))
      (node (ref "D9") (pin "2") (pinfunction "A_2") (pintype "passive"))
      (node (ref "GHB") (pin "1") (pintype "passive"))
      (node (ref "Q3") (pin "4") (pinfunction "G_4") (pintype "passive"))
      (node (ref "R34") (pin "2") (pinfunction "2_2") (pintype "passive"))
      (node (ref "R36") (pin "1") (pinfunction "1_1") (pintype "passive"))
    )
    (net (code "32") (name "Net-(D12-A)") (class "Default")
      (node (ref "C26") (pin "1") (pinfunction "1_1") (pintype "passive"))
      (node (ref "D12") (pin "2") (pinfunction "A_2") (pintype "passive"))
      (node (ref "D14") (pin "1") (pinfunction "K_1") (pintype "passive"))
      (node (ref "GLA") (pin "1") (pintype "passive"))
      (node (ref "Q2") (pin "4") (pinfunction "G_4") (pintype "passive"))
      (node (ref "R43") (pin "2") (pinfunction "2_2") (pintype "passive"))
      (node (ref "R45") (pin "1") (pinfunction "1_1") (pintype "passive"))
    )
    (net (code "33") (name "Net-(D12-K)") (class "Default")
      (node (ref "D12") (pin "1") (pinfunction "K_1") (pintype "passive"))
      (node (ref "R39") (pin "2") (pinfunction "2_2") (pintype "passive"))
    )
    (net (code "34") (name "Net-(D13-A)") (class "Default")
      (node (ref "C27") (pin "1") (pinfunction "1_1") (pintype "passive"))
      (node (ref "D13") (pin "2") (pinfunction "A_2") (pintype "passive"))
      (node (ref "D15") (pin "1") (pinfunction "K_1") (pintype "passive"))
      (node (ref "GLB") (pin "1") (pintype "passive"))
      (node (ref "Q4") (pin "4") (pinfunction "G_4") (pintype "passive"))
      (node (ref "R44") (pin "2") (pinfunction "2_2") (pintype "passive"))
      (node (ref "R46") (pin "1") (pinfunction "1_1") (pintype "passive"))
    )
    (net (code "35") (name "Net-(D13-K)") (class "Default")
      (node (ref "D13") (pin "1") (pinfunction "K_1") (pintype "passive"))
      (node (ref "R40") (pin "2") (pinfunction "2_2") (pintype "passive"))
    )
    (net (code "36") (name "Net-(D14-A)") (class "Default")
      (node (ref "C26") (pin "2") (pinfunction "2_2") (pintype "passive"))
      (node (ref "D14") (pin "2") (pinfunction "A_2") (pintype "passive"))
      (node (ref "NT1") (pin "2") (pinfunction "2_2") (pintype "passive"))
      (node (ref "Q2") (pin "1") (pinfunction "S_1") (pintype "passive"))
      (node (ref "Q2") (pin "2") (pinfunction "S_2") (pintype "passive"))
      (node (ref "Q2") (pin "3") (pinfunction "S_3") (pintype "passive"))
      (node (ref "R45") (pin "2") (pinfunction "2_2") (pintype "passive"))
      (node (ref "R49") (pin "2") (pinfunction "2_2") (pintype "passive"))
    )
    (net (code "37") (name "Net-(D15-A)") (class "Default")
      (node (ref "C27") (pin "2") (pinfunction "2_2") (pintype "passive"))
      (node (ref "D15") (pin "2") (pinfunction "A_2") (pintype "passive"))
      (node (ref "NT2") (pin "2") (pinfunction "2_2") (pintype "passive"))
      (node (ref "Q4") (pin "1") (pinfunction "S_1") (pintype "passive"))
      (node (ref "Q4") (pin "2") (pinfunction "S_2") (pintype "passive"))
      (node (ref "Q4") (pin "3") (pinfunction "S_3") (pintype "passive"))
      (node (ref "R46") (pin "2") (pinfunction "2_2") (pintype "passive"))
      (node (ref "R50") (pin "2") (pinfunction "2_2") (pintype "passive"))
    )
    (net (code "38") (name "Net-(D16-A)") (class "Default")
      (node (ref "C29") (pin "1") (pinfunction "1_1") (pintype "passive"))
      (node (ref "D16") (pin "2") (pinfunction "A_2") (pintype "passive"))
      (node (ref "D17") (pin "1") (pinfunction "K_1") (pintype "passive"))
      (node (ref "GHC") (pin "1") (pintype "passive"))
      (node (ref "Q5") (pin "4") (pinfunction "G_4") (pintype "passive"))
      (node (ref "R54") (pin "2") (pinfunction "2_2") (pintype "passive"))
      (node (ref "R55") (pin "1") (pinfunction "1_1") (pintype "passive"))
    )
    (net (code "39") (name "Net-(D16-K)") (class "Default")
      (node (ref "D16") (pin "1") (pinfunction "K_1") (pintype "passive"))
      (node (ref "R51") (pin "2") (pinfunction "2_2") (pintype "passive"))
    )
    (net (code "40") (name "Net-(D18-A)") (class "Default")
      (node (ref "C32") (pin "1") (pinfunction "1_1") (pintype "passive"))
      (node (ref "D18") (pin "2") (pinfunction "A_2") (pintype "passive"))
      (node (ref "D19") (pin "1") (pinfunction "K_1") (pintype "passive"))
      (node (ref "GLC") (pin "1") (pintype "passive"))
      (node (ref "Q6") (pin "4") (pinfunction "G_4") (pintype "passive"))
      (node (ref "R59") (pin "2") (pinfunction "2_2") (pintype "passive"))
      (node (ref "R61") (pin "1") (pinfunction "1_1") (pintype "passive"))
    )
    (net (code "41") (name "Net-(D18-K)") (class "Default")
      (node (ref "D18") (pin "1") (pinfunction "K_1") (pintype "passive"))
      (node (ref "R57") (pin "2") (pinfunction "2_2") (pintype "passive"))
    )
    (net (code "42") (name "Net-(D19-A)") (class "Default")
      (node (ref "C32") (pin "2") (pinfunction "2_2") (pintype "passive"))
      (node (ref "D19") (pin "2") (pinfunction "A_2") (pintype "passive"))
      (node (ref "NT5") (pin "2") (pinfunction "2_2") (pintype "passive"))
      (node (ref "Q6") (pin "1") (pinfunction "S_1") (pintype "passive"))
      (node (ref "Q6") (pin "2") (pinfunction "S_2") (pintype "passive"))
      (node (ref "Q6") (pin "3") (pinfunction "S_3") (pintype "passive"))
      (node (ref "R61") (pin "2") (pinfunction "2_2") (pintype "passive"))
      (node (ref "R63") (pin "2") (pinfunction "2_2") (pintype "passive"))
    )
    (net (code "43") (name "Net-(U6-VOUT)") (class "Default")
      (node (ref "R60") (pin "2") (pinfunction "2_2") (pintype "passive"))
      (node (ref "U6") (pin "2") (pinfunction "VOUT_2") (pintype "passive"))
    )
    (net (code "44") (name "PVDD") (class "Default")
      (node (ref "C18") (pin "1") (pinfunction "1_1") (pintype "passive"))
      (node (ref "C19") (pin "1") (pinfunction "1_1") (pintype "passive"))
      (node (ref "C28") (pin "1") (pinfunction "1_1") (pintype "passive"))
      (node (ref "Q1") (pin "5") (pinfunction "D_5") (pintype "passive"))
      (node (ref "Q1") (pin "6") (pinfunction "D_6") (pintype "passive"))
      (node (ref "Q1") (pin "7") (pinfunction "D_7") (pintype "passive"))
      (node (ref "Q1") (pin "8") (pinfunction "D_8") (pintype "passive"))
      (node (ref "Q1") (pin "9") (pinfunction "D_9") (pintype "passive"))
      (node (ref "Q3") (pin "5") (pinfunction "D_5") (pintype "passive"))
      (node (ref "Q3") (pin "6") (pinfunction "D_6") (pintype "passive"))
      (node (ref "Q3") (pin "7") (pinfunction "D_7") (pintype "passive"))
      (node (ref "Q3") (pin "8") (pinfunction "D_8") (pintype "passive"))
      (node (ref "Q3") (pin "9") (pinfunction "D_9") (pintype "passive"))
      (node (ref "Q5") (pin "5") (pinfunction "D_5") (pintype "passive"))
      (node (ref "Q5") (pin "6") (pinfunction "D_6") (pintype "passive"))
      (node (ref "Q5") (pin "7") (pinfunction "D_7") (pintype "passive"))
      (node (ref "Q5") (pin "8") (pinfunction "D_8") (pintype "passive"))
      (node (ref "Q5") (pin "9") (pinfunction "D_9") (pintype "passive"))
      (node (ref "R29") (pin "2") (pinfunction "2_2") (pintype "passive"))
      (node (ref "R30") (pin "2") (pinfunction "2_2") (pintype "passive"))
      (node (ref "R52") (pin "2") (pinfunction "2_2") (pintype "passive"))
    )
  )
)
